# OpAmpAmplifier.net
KiCad netlist of a schematic drawn in EAGLE
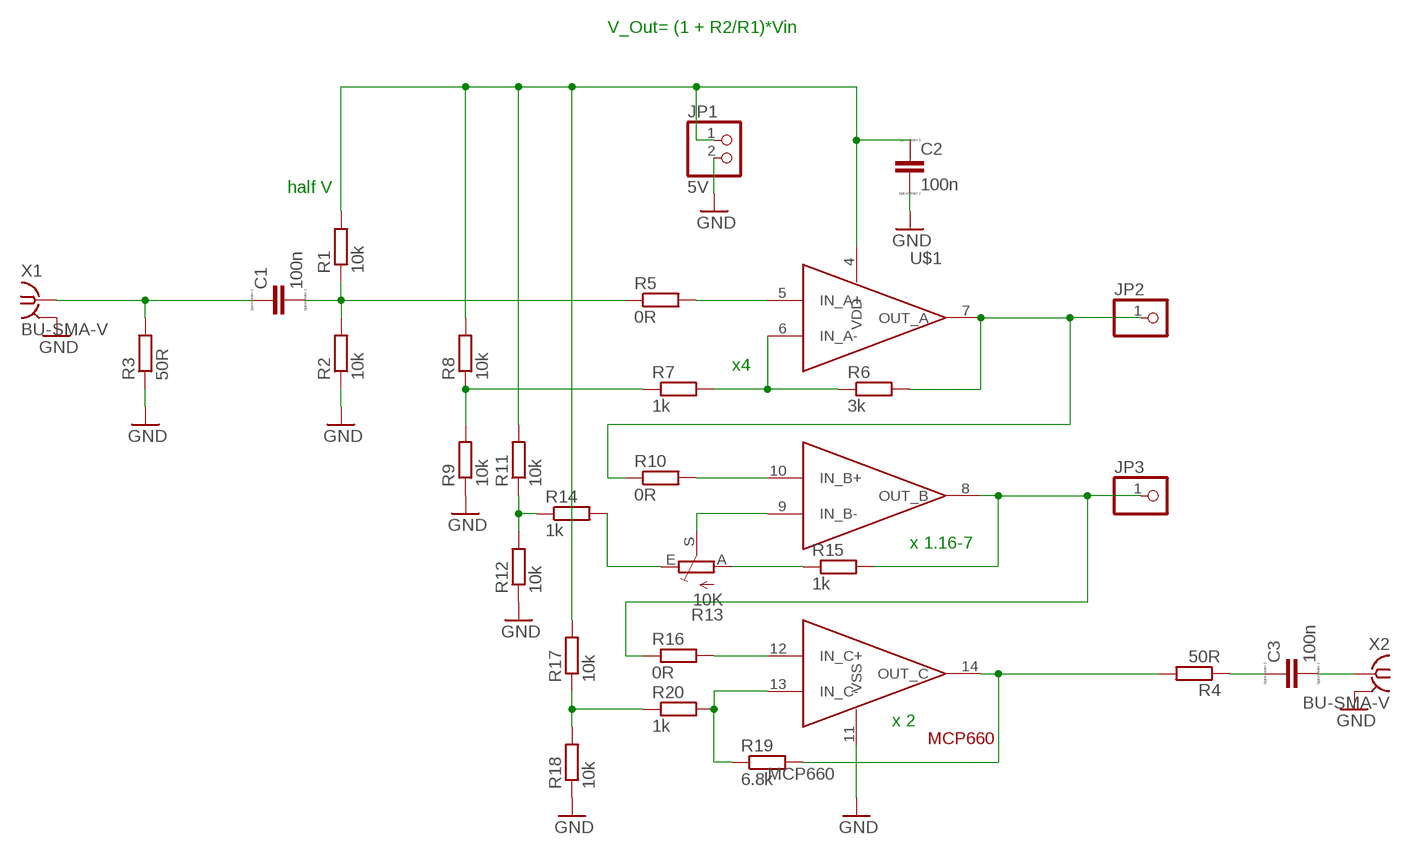
[diagram p0: schematic, sheet 1]

(export (version "E")
  (design (tool "Eeschema 10.0.6"))
  (components
    (comp (ref "C1")
      (value "100n")
      (footprint "eagle-import:C0805")
      (libsource (lib "eagle-import") (part "C_SMD"))
    )
    (comp (ref "C2")
      (value "100n")
      (footprint "eagle-import:C0805")
      (libsource (lib "eagle-import") (part "C_SMD"))
    )
    (comp (ref "C3")
      (value "100n")
      (footprint "eagle-import:C0805")
      (libsource (lib "eagle-import") (part "C_SMD"))
    )
    (comp (ref "JP1")
      (value "5V")
      (footprint "eagle-import:1X02")
      (libsource (lib "eagle-import") (part "PINHD-1X2"))
    )
    (comp (ref "JP2")
      (value "PINHD-1X1")
      (footprint "eagle-import:1X01")
      (libsource (lib "eagle-import") (part "PINHD-1X1"))
    )
    (comp (ref "JP3")
      (value "PINHD-1X1")
      (footprint "eagle-import:1X01")
      (libsource (lib "eagle-import") (part "PINHD-1X1"))
    )
    (comp (ref "R1")
      (value "10k")
      (footprint "eagle-import:R0805")
      (libsource (lib "eagle-import") (part "R-EU_R0805"))
    )
    (comp (ref "R2")
      (value "10k")
      (footprint "eagle-import:R0805")
      (libsource (lib "eagle-import") (part "R-EU_R0805"))
    )
    (comp (ref "R3")
      (value "50R")
      (footprint "eagle-import:R0805")
      (libsource (lib "eagle-import") (part "R-EU_R0805"))
    )
    (comp (ref "R4")
      (value "50R")
      (footprint "eagle-import:R0805")
      (libsource (lib "eagle-import") (part "R-EU_R0805"))
    )
    (comp (ref "R5")
      (value "0R")
      (footprint "eagle-import:R0805")
      (libsource (lib "eagle-import") (part "R-EU_R0805"))
    )
    (comp (ref "R6")
      (value "3k")
      (footprint "eagle-import:R0805")
      (libsource (lib "eagle-import") (part "R-EU_R0805"))
    )
    (comp (ref "R7")
      (value "1k")
      (footprint "eagle-import:R0805")
      (libsource (lib "eagle-import") (part "R-EU_R0805"))
    )
    (comp (ref "R8")
      (value "10k")
      (footprint "eagle-import:R0805")
      (libsource (lib "eagle-import") (part "R-EU_R0805"))
    )
    (comp (ref "R9")
      (value "10k")
      (footprint "eagle-import:R0805")
      (libsource (lib "eagle-import") (part "R-EU_R0805"))
    )
    (comp (ref "R10")
      (value "0R")
      (footprint "eagle-import:R0805")
      (libsource (lib "eagle-import") (part "R-EU_R0805"))
    )
    (comp (ref "R11")
      (value "10k")
      (footprint "eagle-import:R0805")
      (libsource (lib "eagle-import") (part "R-EU_R0805"))
    )
    (comp (ref "R12")
      (value "10k")
      (footprint "eagle-import:R0805")
      (libsource (lib "eagle-import") (part "R-EU_R0805"))
    )
    (comp (ref "R13")
      (value "10K")
      (footprint "eagle-import:CA6V")
      (libsource (lib "eagle-import") (part "TRIM_EU-CA6V"))
    )
    (comp (ref "R14")
      (value "1k")
      (footprint "eagle-import:R0805")
      (libsource (lib "eagle-import") (part "R-EU_R0805"))
    )
    (comp (ref "R15")
      (value "1k")
      (footprint "eagle-import:R0805")
      (libsource (lib "eagle-import") (part "R-EU_R0805"))
    )
    (comp (ref "R16")
      (value "0R")
      (footprint "eagle-import:R0805")
      (libsource (lib "eagle-import") (part "R-EU_R0805"))
    )
    (comp (ref "R17")
      (value "10k")
      (footprint "eagle-import:R0805")
      (libsource (lib "eagle-import") (part "R-EU_R0805"))
    )
    (comp (ref "R18")
      (value "10k")
      (footprint "eagle-import:R0805")
      (libsource (lib "eagle-import") (part "R-EU_R0805"))
    )
    (comp (ref "R19")
      (value "6.8k")
      (footprint "eagle-import:R0805")
      (libsource (lib "eagle-import") (part "R-EU_R0805"))
    )
    (comp (ref "R20")
      (value "1k")
      (footprint "eagle-import:R0805")
      (libsource (lib "eagle-import") (part "R-EU_R0805"))
    )
    (comp (ref "U$1")
      (value "MCP660")
      (footprint "eagle-import:SO14")
      (libsource (lib "eagle-import") (part "MCP660"))
    )
    (comp (ref "X1")
      (value "BU-SMA-V")
      (footprint "eagle-import:BU-SMA-V")
      (libsource (lib "eagle-import") (part "BU-SMA-V"))
    )
    (comp (ref "X2")
      (value "BU-SMA-V")
      (footprint "eagle-import:BU-SMA-V")
      (libsource (lib "eagle-import") (part "BU-SMA-V"))
    )
  )
  (nets
    (net (code "1") (name "GND") (class "Default")
      (node (ref "C2") (pin "2") (pinfunction "2_2") (pintype "passive"))
      (node (ref "JP1") (pin "2") (pinfunction "2_2") (pintype "passive"))
      (node (ref "R12") (pin "1") (pinfunction "1_1") (pintype "passive"))
      (node (ref "R18") (pin "1") (pinfunction "1_1") (pintype "passive"))
      (node (ref "R2") (pin "1") (pinfunction "1_1") (pintype "passive"))
      (node (ref "R3") (pin "1") (pinfunction "1_1") (pintype "passive"))
      (node (ref "R9") (pin "1") (pinfunction "1_1") (pintype "passive"))
      (node (ref "U$1") (pin "11") (pinfunction "VSS_11") (pintype "bidirectional"))
      (node (ref "X1") (pin "2") (pinfunction "2_2") (pintype "passive"))
      (node (ref "X1") (pin "3") (pinfunction "2_3") (pintype "passive"))
      (node (ref "X1") (pin "4") (pinfunction "2_4") (pintype "passive"))
      (node (ref "X1") (pin "5") (pinfunction "2_5") (pintype "passive"))
      (node (ref "X2") (pin "2") (pinfunction "2_2") (pintype "passive"))
      (node (ref "X2") (pin "3") (pinfunction "2_3") (pintype "passive"))
      (node (ref "X2") (pin "4") (pinfunction "2_4") (pintype "passive"))
      (node (ref "X2") (pin "5") (pinfunction "2_5") (pintype "passive"))
    )
    (net (code "2") (name "Net-(C1-Pad1)") (class "Default")
      (node (ref "C1") (pin "1") (pinfunction "1_1") (pintype "passive"))
      (node (ref "R3") (pin "2") (pinfunction "2_2") (pintype "passive"))
      (node (ref "X1") (pin "1") (pinfunction "1_1") (pintype "passive"))
    )
    (net (code "3") (name "Net-(C1-Pad2)") (class "Default")
      (node (ref "C1") (pin "2") (pinfunction "2_2") (pintype "passive"))
      (node (ref "R1") (pin "1") (pinfunction "1_1") (pintype "passive"))
      (node (ref "R2") (pin "2") (pinfunction "2_2") (pintype "passive"))
      (node (ref "R5") (pin "1") (pinfunction "1_1") (pintype "passive"))
    )
    (net (code "4") (name "Net-(C3-Pad1)") (class "Default")
      (node (ref "C3") (pin "1") (pinfunction "1_1") (pintype "passive"))
      (node (ref "R4") (pin "1") (pinfunction "1_1") (pintype "passive"))
    )
    (net (code "5") (name "Net-(C3-Pad2)") (class "Default")
      (node (ref "C3") (pin "2") (pinfunction "2_2") (pintype "passive"))
      (node (ref "X2") (pin "1") (pinfunction "1_1") (pintype "passive"))
    )
    (net (code "6") (name "Net-(R7-Pad1)") (class "Default")
      (node (ref "R7") (pin "1") (pinfunction "1_1") (pintype "passive"))
      (node (ref "R8") (pin "1") (pinfunction "1_1") (pintype "passive"))
      (node (ref "R9") (pin "2") (pinfunction "2_2") (pintype "passive"))
    )
    (net (code "7") (name "Net-(R11-Pad1)") (class "Default")
      (node (ref "R11") (pin "1") (pinfunction "1_1") (pintype "passive"))
      (node (ref "R12") (pin "2") (pinfunction "2_2") (pintype "passive"))
      (node (ref "R14") (pin "1") (pinfunction "1_1") (pintype "passive"))
    )
    (net (code "8") (name "Net-(R13-PadA)") (class "Default")
      (node (ref "R13") (pin "A") (pinfunction "A_A") (pintype "passive"))
      (node (ref "R15") (pin "1") (pinfunction "1_1") (pintype "passive"))
    )
    (net (code "9") (name "Net-(R13-PadE)") (class "Default")
      (node (ref "R13") (pin "E") (pinfunction "E_E") (pintype "passive"))
      (node (ref "R14") (pin "2") (pinfunction "2_2") (pintype "passive"))
    )
    (net (code "10") (name "Net-(R17-Pad1)") (class "Default")
      (node (ref "R17") (pin "1") (pinfunction "1_1") (pintype "passive"))
      (node (ref "R18") (pin "2") (pinfunction "2_2") (pintype "passive"))
      (node (ref "R20") (pin "1") (pinfunction "1_1") (pintype "passive"))
    )
    (net (code "11") (name "Net-(U$1-IN_A+)") (class "Default")
      (node (ref "R5") (pin "2") (pinfunction "2_2") (pintype "passive"))
      (node (ref "U$1") (pin "5") (pinfunction "IN_A+_5") (pintype "bidirectional"))
    )
    (net (code "12") (name "Net-(U$1-IN_A-)") (class "Default")
      (node (ref "R6") (pin "1") (pinfunction "1_1") (pintype "passive"))
      (node (ref "R7") (pin "2") (pinfunction "2_2") (pintype "passive"))
      (node (ref "U$1") (pin "6") (pinfunction "IN_A-_6") (pintype "bidirectional"))
    )
    (net (code "13") (name "Net-(U$1-IN_B+)") (class "Default")
      (node (ref "R10") (pin "2") (pinfunction "2_2") (pintype "passive"))
      (node (ref "U$1") (pin "10") (pinfunction "IN_B+_10") (pintype "bidirectional"))
    )
    (net (code "14") (name "Net-(U$1-IN_B-)") (class "Default")
      (node (ref "R13") (pin "S") (pinfunction "S_S") (pintype "passive"))
      (node (ref "U$1") (pin "9") (pinfunction "IN_B-_9") (pintype "bidirectional"))
    )
    (net (code "15") (name "Net-(U$1-IN_C+)") (class "Default")
      (node (ref "R16") (pin "2") (pinfunction "2_2") (pintype "passive"))
      (node (ref "U$1") (pin "12") (pinfunction "IN_C+_12") (pintype "bidirectional"))
    )
    (net (code "16") (name "Net-(U$1-IN_C-)") (class "Default")
      (node (ref "R19") (pin "1") (pinfunction "1_1") (pintype "passive"))
      (node (ref "R20") (pin "2") (pinfunction "2_2") (pintype "passive"))
      (node (ref "U$1") (pin "13") (pinfunction "IN_C-_13") (pintype "bidirectional"))
    )
    (net (code "17") (name "Net-(U$1-OUT_A)") (class "Default")
      (node (ref "JP2") (pin "1") (pinfunction "1_1") (pintype "passive"))
      (node (ref "R10") (pin "1") (pinfunction "1_1") (pintype "passive"))
      (node (ref "R6") (pin "2") (pinfunction "2_2") (pintype "passive"))
      (node (ref "U$1") (pin "7") (pinfunction "OUT_A_7") (pintype "bidirectional"))
    )
    (net (code "18") (name "Net-(U$1-OUT_B)") (class "Default")
      (node (ref "JP3") (pin "1") (pinfunction "1_1") (pintype "passive"))
      (node (ref "R15") (pin "2") (pinfunction "2_2") (pintype "passive"))
      (node (ref "R16") (pin "1") (pinfunction "1_1") (pintype "passive"))
      (node (ref "U$1") (pin "8") (pinfunction "OUT_B_8") (pintype "bidirectional"))
    )
    (net (code "19") (name "Net-(U$1-OUT_C)") (class "Default")
      (node (ref "R19") (pin "2") (pinfunction "2_2") (pintype "passive"))
      (node (ref "R4") (pin "2") (pinfunction "2_2") (pintype "passive"))
      (node (ref "U$1") (pin "14") (pinfunction "OUT_C_14") (pintype "bidirectional"))
    )
    (net (code "20") (name "Net-(U$1-VDD)") (class "Default")
      (node (ref "C2") (pin "1") (pinfunction "1_1") (pintype "passive"))
      (node (ref "JP1") (pin "1") (pinfunction "1_1") (pintype "passive"))
      (node (ref "R1") (pin "2") (pinfunction "2_2") (pintype "passive"))
      (node (ref "R11") (pin "2") (pinfunction "2_2") (pintype "passive"))
      (node (ref "R17") (pin "2") (pinfunction "2_2") (pintype "passive"))
      (node (ref "R8") (pin "2") (pinfunction "2_2") (pintype "passive"))
      (node (ref "U$1") (pin "4") (pinfunction "VDD_4") (pintype "bidirectional"))
    )
  )
)
